# GPS.net
KiCad netlist of a schematic drawn in Altium Designer
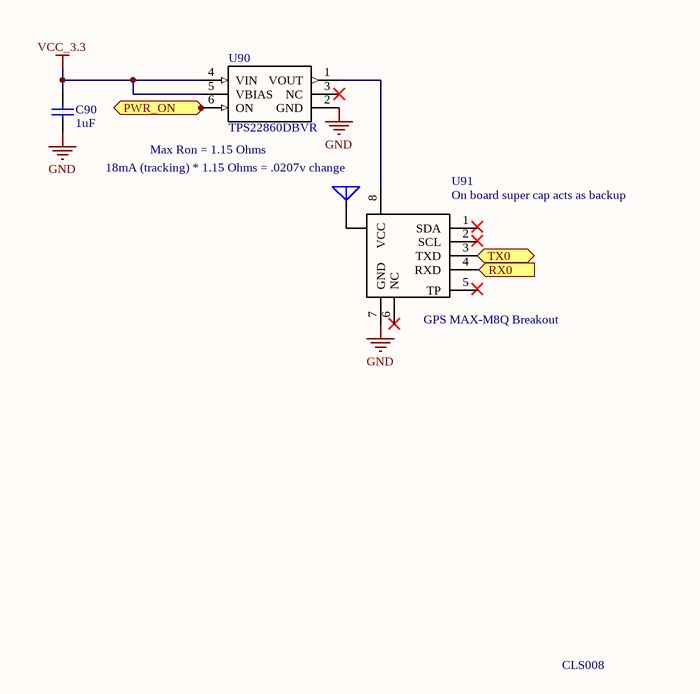
[diagram p0: GPS.SchDoc]

(export (version "E")
  (design (tool "Eeschema 10.0.6"))
  (components
    (comp (ref "C90")
      (value "1uF")
      (footprint "0805_CHIP_FP")
      (fields
        (field (name "MANUFACTURER") "Samsung Electro-Mechanics")
        (field (name "MANUFACTURER PART NUMBER") "CL21A105KOFNNNE")
        (field (name "VENDOR PART NUMBER") "1276-2888-1-ND")
      )
      (libsource (lib "GenericSymbols") (part "Capacitor_unpolarized_0603"))
    )
    (comp (ref "U90")
      (value "TPS22860DBVR")
      (footprint "SOT95P279X145-6N")
      (description "TPS22860 Ultra-low leakage load switch 6-SOT-23 -40 to 85")
      (fields
        (field (name "MANUFACTURER") "Texas Instruments")
        (field (name "VENDOR PART NUMBER") "296-43982-1-ND")
      )
      (libsource (lib "TPS22860DBVR") (part "TPS22860DBVR"))
    )
    (comp (ref "U91")
      (value "GPS MAX-M8Q Breakout")
      (footprint "HDR1X8")
      (description "uBLOX MAX-M8Q GPS Breakout for Active")
      (fields
        (field (name "MANUFACTURER") "Airspy")
        (field (name "MANUFACTURER PART NUMBER") "UPU-uBLOX M8Q3A SMA")
      )
      (libsource (lib "GenericSymbols") (part "GPS MAX-M8Q Breakout"))
    )
  )
  (nets
    (net (code "2") (name "/RX0") (class "Default")
      (node (ref "U91") (pin "4") (pinfunction "RXD_4") (pintype "passive"))
    )
    (net (code "3") (name "/TX0") (class "Default")
      (node (ref "U91") (pin "3") (pinfunction "TXD_3") (pintype "passive"))
    )
    (net (code "4") (name "GND") (class "Default")
      (node (ref "C90") (pin "2") (pinfunction "2_2") (pintype "passive"))
      (node (ref "U90") (pin "2") (pinfunction "GND_2") (pintype "passive"))
      (node (ref "U91") (pin "7") (pinfunction "GND_7") (pintype "passive"))
    )
    (net (code "5") (name "Net-(U90-VOUT)") (class "Default")
      (node (ref "U90") (pin "1") (pinfunction "VOUT_1") (pintype "output"))
      (node (ref "U91") (pin "8") (pinfunction "VCC_8") (pintype "passive"))
    )
    (net (code "6") (name "VCC_3.3") (class "Default")
      (node (ref "C90") (pin "1") (pinfunction "1_1") (pintype "passive"))
      (node (ref "U90") (pin "4") (pinfunction "VIN_4") (pintype "input"))
      (node (ref "U90") (pin "5") (pinfunction "VBIAS_5") (pintype "power_in"))
    )
    (net (code "7") (name "unconnected-(U90-NC-Pad3)") (class "Default")
      (node (ref "U90") (pin "3") (pinfunction "NC_3") (pintype "passive+no_connect"))
    )
    (net (code "8") (name "unconnected-(U90-ON-Pad6)") (class "Default")
      (node (ref "U90") (pin "6") (pinfunction "ON_6") (pintype "input"))
    )
    (net (code "9") (name "unconnected-(U91-A-Pad9)") (class "Default")
      (node (ref "U91") (pin "9") (pinfunction "A_9") (pintype "passive"))
    )
    (net (code "10") (name "unconnected-(U91-NC-Pad6)") (class "Default")
      (node (ref "U91") (pin "6") (pinfunction "NC_6") (pintype "passive"))
    )
    (net (code "11") (name "unconnected-(U91-SCL-Pad2)") (class "Default")
      (node (ref "U91") (pin "2") (pinfunction "SCL_2") (pintype "passive"))
    )
    (net (code "12") (name "unconnected-(U91-SDA-Pad1)") (class "Default")
      (node (ref "U91") (pin "1") (pinfunction "SDA_1") (pintype "passive"))
    )
    (net (code "13") (name "unconnected-(U91-TP-Pad5)") (class "Default")
      (node (ref "U91") (pin "5") (pinfunction "TP_5") (pintype "passive"))
    )
  )
)
